# MCU.net
KiCad netlist of a schematic drawn in Altium Designer
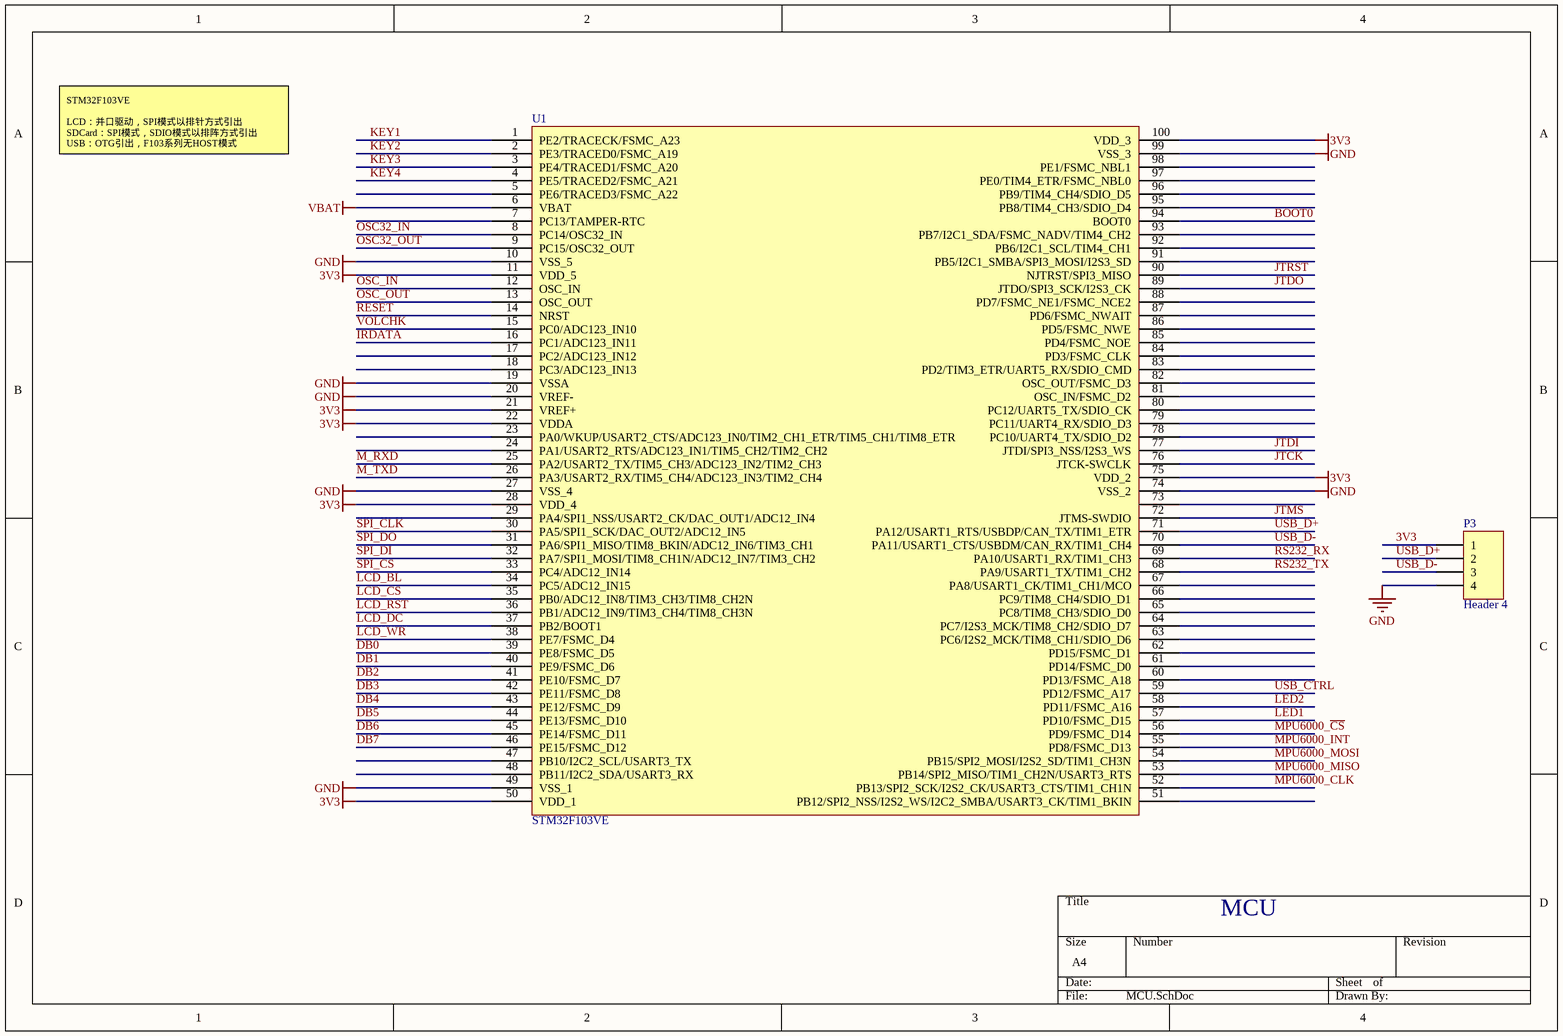
[diagram p0: MCU.SchDoc]

(export (version "E")
  (design (tool "Eeschema 10.0.6"))
  (components
    (comp (ref "P3")
      (value "Header 4")
      (footprint "HDR1X4")
      (description "Header, 4-Pin")
      (fields (field (name "PUBLISHER") "Altium Limited"))
      (libsource (lib "Miscellaneous Connectors") (part "Header 4"))
    )
    (comp (ref "U1")
      (value "STM32F103VE")
      (footprint "LQFP100_M")
      (libsource (lib "STM32F103VE") (part "STM32F103VE"))
    )
  )
  (nets
    (net (code "1") (name "/BOOT0") (class "Default")
      (node (ref "U1") (pin "94") (pinfunction "BOOT0_94") (pintype "passive"))
    )
    (net (code "2") (name "/DB0") (class "Default")
      (node (ref "U1") (pin "39") (pinfunction "PE8/FSMC_D5_39") (pintype "passive"))
    )
    (net (code "3") (name "/DB1") (class "Default")
      (node (ref "U1") (pin "40") (pinfunction "PE9/FSMC_D6_40") (pintype "passive"))
    )
    (net (code "4") (name "/DB2") (class "Default")
      (node (ref "U1") (pin "41") (pinfunction "PE10/FSMC_D7_41") (pintype "passive"))
    )
    (net (code "5") (name "/DB3") (class "Default")
      (node (ref "U1") (pin "42") (pinfunction "PE11/FSMC_D8_42") (pintype "passive"))
    )
    (net (code "6") (name "/DB4") (class "Default")
      (node (ref "U1") (pin "43") (pinfunction "PE12/FSMC_D9_43") (pintype "passive"))
    )
    (net (code "7") (name "/DB5") (class "Default")
      (node (ref "U1") (pin "44") (pinfunction "PE13/FSMC_D10_44") (pintype "passive"))
    )
    (net (code "8") (name "/DB6") (class "Default")
      (node (ref "U1") (pin "45") (pinfunction "PE14/FSMC_D11_45") (pintype "passive"))
    )
    (net (code "9") (name "/DB7") (class "Default")
      (node (ref "U1") (pin "46") (pinfunction "PE15/FSMC_D12_46") (pintype "passive"))
    )
    (net (code "10") (name "/IRDATA") (class "Default")
      (node (ref "U1") (pin "16") (pinfunction "PC1/ADC123_IN11_16") (pintype "passive"))
    )
    (net (code "11") (name "/JTCK") (class "Default")
      (node (ref "U1") (pin "76") (pinfunction "JTCK-SWCLK_76") (pintype "passive"))
    )
    (net (code "12") (name "/JTDI") (class "Default")
      (node (ref "U1") (pin "77") (pinfunction "JTDI/SPI3_NSS/I2S3_WS_77") (pintype "passive"))
    )
    (net (code "13") (name "/JTDO") (class "Default")
      (node (ref "U1") (pin "89") (pinfunction "JTDO/SPI3_SCK/I2S3_CK_89") (pintype "passive"))
    )
    (net (code "14") (name "/JTMS") (class "Default")
      (node (ref "U1") (pin "72") (pinfunction "JTMS-SWDIO_72") (pintype "passive"))
    )
    (net (code "15") (name "/JTRST") (class "Default")
      (node (ref "U1") (pin "90") (pinfunction "NJTRST/SPI3_MISO_90") (pintype "passive"))
    )
    (net (code "16") (name "/KEY1") (class "Default")
      (node (ref "U1") (pin "1") (pinfunction "PE2/TRACECK/FSMC_A23_1") (pintype "passive"))
    )
    (net (code "17") (name "/KEY2") (class "Default")
      (node (ref "U1") (pin "2") (pinfunction "PE3/TRACED0/FSMC_A19_2") (pintype "passive"))
    )
    (net (code "18") (name "/KEY3") (class "Default")
      (node (ref "U1") (pin "3") (pinfunction "PE4/TRACED1/FSMC_A20_3") (pintype "passive"))
    )
    (net (code "19") (name "/KEY4") (class "Default")
      (node (ref "U1") (pin "4") (pinfunction "PE5/TRACED2/FSMC_A21_4") (pintype "passive"))
    )
    (net (code "20") (name "/LCD_BL") (class "Default")
      (node (ref "U1") (pin "34") (pinfunction "PC5/ADC12_IN15_34") (pintype "passive"))
    )
    (net (code "21") (name "/LCD_CS") (class "Default")
      (node (ref "U1") (pin "35") (pinfunction "PB0/ADC12_IN8/TIM3_CH3/TIM8_CH2N_35") (pintype "passive"))
    )
    (net (code "22") (name "/LCD_DC") (class "Default")
      (node (ref "U1") (pin "37") (pinfunction "PB2/BOOT1_37") (pintype "passive"))
    )
    (net (code "23") (name "/LCD_RST") (class "Default")
      (node (ref "U1") (pin "36") (pinfunction "PB1/ADC12_IN9/TIM3_CH4/TIM8_CH3N_36") (pintype "passive"))
    )
    (net (code "24") (name "/LCD_WR") (class "Default")
      (node (ref "U1") (pin "38") (pinfunction "PE7/FSMC_D4_38") (pintype "passive"))
    )
    (net (code "25") (name "/LED1") (class "Default")
      (node (ref "U1") (pin "57") (pinfunction "PD10/FSMC_D15_57") (pintype "passive"))
    )
    (net (code "26") (name "/LED2") (class "Default")
      (node (ref "U1") (pin "58") (pinfunction "PD11/FSMC_A16_58") (pintype "passive"))
    )
    (net (code "27") (name "/MPU6000_CLK") (class "Default")
      (node (ref "U1") (pin "52") (pinfunction "PB13/SPI2_SCK/I2S2_CK/USART3_CTS/TIM1_CH1N_52") (pintype "passive"))
    )
    (net (code "28") (name "/MPU6000_INT") (class "Default")
      (node (ref "U1") (pin "55") (pinfunction "PD8/FSMC_D13_55") (pintype "passive"))
    )
    (net (code "29") (name "/MPU6000_MISO") (class "Default")
      (node (ref "U1") (pin "53") (pinfunction "PB14/SPI2_MISO/TIM1_CH2N/USART3_RTS_53") (pintype "passive"))
    )
    (net (code "30") (name "/MPU6000_MOSI") (class "Default")
      (node (ref "U1") (pin "54") (pinfunction "PB15/SPI2_MOSI/I2S2_SD/TIM1_CH3N_54") (pintype "passive"))
    )
    (net (code "31") (name "/MPU6000_~{CS}") (class "Default")
      (node (ref "U1") (pin "56") (pinfunction "PD9/FSMC_D14_56") (pintype "passive"))
    )
    (net (code "32") (name "/M_RXD") (class "Default")
      (node (ref "U1") (pin "25") (pinfunction "PA2/USART2_TX/TIM5_CH3/ADC123_IN2/TIM2_CH3_25") (pintype "passive"))
    )
    (net (code "33") (name "/M_TXD") (class "Default")
      (node (ref "U1") (pin "26") (pinfunction "PA3/USART2_RX/TIM5_CH4/ADC123_IN3/TIM2_CH4_26") (pintype "passive"))
    )
    (net (code "34") (name "/OSC32_IN") (class "Default")
      (node (ref "U1") (pin "8") (pinfunction "PC14/OSC32_IN_8") (pintype "passive"))
    )
    (net (code "35") (name "/OSC32_OUT") (class "Default")
      (node (ref "U1") (pin "9") (pinfunction "PC15/OSC32_OUT_9") (pintype "passive"))
    )
    (net (code "36") (name "/OSC_IN") (class "Default")
      (node (ref "U1") (pin "12") (pinfunction "OSC_IN_12") (pintype "passive"))
    )
    (net (code "37") (name "/OSC_OUT") (class "Default")
      (node (ref "U1") (pin "13") (pinfunction "OSC_OUT_13") (pintype "passive"))
    )
    (net (code "38") (name "/RESET") (class "Default")
      (node (ref "U1") (pin "14") (pinfunction "NRST_14") (pintype "passive"))
    )
    (net (code "39") (name "/RS232_RX") (class "Default")
      (node (ref "U1") (pin "69") (pinfunction "PA10/USART1_RX/TIM1_CH3_69") (pintype "passive"))
    )
    (net (code "40") (name "/RS232_TX") (class "Default")
      (node (ref "U1") (pin "68") (pinfunction "PA9/USART1_TX/TIM1_CH2_68") (pintype "passive"))
    )
    (net (code "41") (name "/SPI_CLK") (class "Default")
      (node (ref "U1") (pin "30") (pinfunction "PA5/SPI1_SCK/DAC_OUT2/ADC12_IN5_30") (pintype "passive"))
    )
    (net (code "42") (name "/SPI_DI") (class "Default")
      (node (ref "U1") (pin "32") (pinfunction "PA7/SPI1_MOSI/TIM8_CH1N/ADC12_IN7/TIM3_CH2_32") (pintype "passive"))
    )
    (net (code "43") (name "/SPI_DO") (class "Default")
      (node (ref "U1") (pin "31") (pinfunction "PA6/SPI1_MISO/TIM8_BKIN/ADC12_IN6/TIM3_CH1_31") (pintype "passive"))
    )
    (net (code "44") (name "/SPI_~{CS}") (class "Default")
      (node (ref "U1") (pin "33") (pinfunction "PC4/ADC12_IN14_33") (pintype "passive"))
    )
    (net (code "45") (name "/USB_CTRL") (class "Default")
      (node (ref "U1") (pin "59") (pinfunction "PD12/FSMC_A17_59") (pintype "passive"))
    )
    (net (code "46") (name "/USB_D+") (class "Default")
      (node (ref "P3") (pin "2") (pinfunction "2_2") (pintype "passive"))
      (node (ref "U1") (pin "71") (pinfunction "PA12/USART1_RTS/USBDP/CAN_TX/TIM1_ETR_71") (pintype "passive"))
    )
    (net (code "47") (name "/USB_D-") (class "Default")
      (node (ref "P3") (pin "3") (pinfunction "3_3") (pintype "passive"))
      (node (ref "U1") (pin "70") (pinfunction "PA11/USART1_CTS/USBDM/CAN_RX/TIM1_CH4_70") (pintype "passive"))
    )
    (net (code "48") (name "/VOLCHK") (class "Default")
      (node (ref "U1") (pin "15") (pinfunction "PC0/ADC123_IN10_15") (pintype "passive"))
    )
    (net (code "49") (name "3V3") (class "Default")
      (node (ref "P3") (pin "1") (pinfunction "1_1") (pintype "passive"))
      (node (ref "U1") (pin "100") (pinfunction "VDD_3_100") (pintype "passive"))
      (node (ref "U1") (pin "11") (pinfunction "VDD_5_11") (pintype "passive"))
      (node (ref "U1") (pin "21") (pinfunction "VREF+_21") (pintype "passive"))
      (node (ref "U1") (pin "22") (pinfunction "VDDA_22") (pintype "passive"))
      (node (ref "U1") (pin "28") (pinfunction "VDD_4_28") (pintype "passive"))
      (node (ref "U1") (pin "50") (pinfunction "VDD_1_50") (pintype "passive"))
      (node (ref "U1") (pin "75") (pinfunction "VDD_2_75") (pintype "passive"))
    )
    (net (code "50") (name "GND") (class "Default")
      (node (ref "P3") (pin "4") (pinfunction "4_4") (pintype "passive"))
      (node (ref "U1") (pin "10") (pinfunction "VSS_5_10") (pintype "passive"))
      (node (ref "U1") (pin "19") (pinfunction "VSSA_19") (pintype "passive"))
      (node (ref "U1") (pin "20") (pinfunction "VREF-_20") (pintype "passive"))
      (node (ref "U1") (pin "27") (pinfunction "VSS_4_27") (pintype "passive"))
      (node (ref "U1") (pin "49") (pinfunction "VSS_1_49") (pintype "passive"))
      (node (ref "U1") (pin "74") (pinfunction "VSS_2_74") (pintype "passive"))
      (node (ref "U1") (pin "99") (pinfunction "VSS_3_99") (pintype "passive"))
    )
    (net (code "51") (name "VBAT") (class "Default")
      (node (ref "U1") (pin "6") (pinfunction "VBAT_6") (pintype "passive"))
    )
    (net (code "52") (name "unconnected-(U1-OSC_IN{slash}FSMC_D2-Pad81)") (class "Default")
      (node (ref "U1") (pin "81") (pinfunction "OSC_IN/FSMC_D2_81") (pintype "passive"))
    )
    (net (code "53") (name "unconnected-(U1-OSC_OUT{slash}FSMC_D3-Pad82)") (class "Default")
      (node (ref "U1") (pin "82") (pinfunction "OSC_OUT/FSMC_D3_82") (pintype "passive"))
    )
    (net (code "54") (name "unconnected-(U1-PA0{slash}WKUP{slash}USART2_CTS{slash}ADC123_IN0{slash}TIM2_CH1_ETR{slash}TIM5_CH1{slash}TIM8_ETR-Pad23)") (class "Default")
      (node (ref "U1") (pin "23") (pinfunction "PA0/WKUP/USART2_CTS/ADC123_IN0/TIM2_CH1_ETR/TIM5_CH1/TIM8_ETR_23") (pintype "passive"))
    )
    (net (code "55") (name "unconnected-(U1-PA1{slash}USART2_RTS{slash}ADC123_IN1{slash}TIM5_CH2{slash}TIM2_CH2-Pad24)") (class "Default")
      (node (ref "U1") (pin "24") (pinfunction "PA1/USART2_RTS/ADC123_IN1/TIM5_CH2/TIM2_CH2_24") (pintype "passive"))
    )
    (net (code "56") (name "unconnected-(U1-PA4{slash}SPI1_NSS{slash}USART2_CK{slash}DAC_OUT1{slash}ADC12_IN4-Pad29)") (class "Default")
      (node (ref "U1") (pin "29") (pinfunction "PA4/SPI1_NSS/USART2_CK/DAC_OUT1/ADC12_IN4_29") (pintype "passive"))
    )
    (net (code "57") (name "unconnected-(U1-PA8{slash}USART1_CK{slash}TIM1_CH1{slash}MCO-Pad67)") (class "Default")
      (node (ref "U1") (pin "67") (pinfunction "PA8/USART1_CK/TIM1_CH1/MCO_67") (pintype "passive"))
    )
    (net (code "58") (name "unconnected-(U1-PB5{slash}I2C1_SMBA{slash}SPI3_MOSI{slash}I2S3_SD-Pad91)") (class "Default")
      (node (ref "U1") (pin "91") (pinfunction "PB5/I2C1_SMBA/SPI3_MOSI/I2S3_SD_91") (pintype "passive"))
    )
    (net (code "59") (name "unconnected-(U1-PB6{slash}I2C1_SCL{slash}TIM4_CH1-Pad92)") (class "Default")
      (node (ref "U1") (pin "92") (pinfunction "PB6/I2C1_SCL/TIM4_CH1_92") (pintype "passive"))
    )
    (net (code "60") (name "unconnected-(U1-PB7{slash}I2C1_SDA{slash}FSMC_NADV{slash}TIM4_CH2-Pad93)") (class "Default")
      (node (ref "U1") (pin "93") (pinfunction "PB7/I2C1_SDA/FSMC_NADV/TIM4_CH2_93") (pintype "passive"))
    )
    (net (code "61") (name "unconnected-(U1-PB8{slash}TIM4_CH3{slash}SDIO_D4-Pad95)") (class "Default")
      (node (ref "U1") (pin "95") (pinfunction "PB8/TIM4_CH3/SDIO_D4_95") (pintype "passive"))
    )
    (net (code "62") (name "unconnected-(U1-PB9{slash}TIM4_CH4{slash}SDIO_D5-Pad96)") (class "Default")
      (node (ref "U1") (pin "96") (pinfunction "PB9/TIM4_CH4/SDIO_D5_96") (pintype "passive"))
    )
    (net (code "63") (name "unconnected-(U1-PB10{slash}I2C2_SCL{slash}USART3_TX-Pad47)") (class "Default")
      (node (ref "U1") (pin "47") (pinfunction "PB10/I2C2_SCL/USART3_TX_47") (pintype "passive"))
    )
    (net (code "64") (name "unconnected-(U1-PB11{slash}I2C2_SDA{slash}USART3_RX-Pad48)") (class "Default")
      (node (ref "U1") (pin "48") (pinfunction "PB11/I2C2_SDA/USART3_RX_48") (pintype "passive"))
    )
    (net (code "65") (name "unconnected-(U1-PB12{slash}SPI2_NSS{slash}I2S2_WS{slash}I2C2_SMBA{slash}USART3_CK{slash}TIM1_BKIN-Pad51)") (class "Default")
      (node (ref "U1") (pin "51") (pinfunction "PB12/SPI2_NSS/I2S2_WS/I2C2_SMBA/USART3_CK/TIM1_BKIN_51") (pintype "passive"))
    )
    (net (code "66") (name "unconnected-(U1-PC2{slash}ADC123_IN12-Pad17)") (class "Default")
      (node (ref "U1") (pin "17") (pinfunction "PC2/ADC123_IN12_17") (pintype "passive"))
    )
    (net (code "67") (name "unconnected-(U1-PC3{slash}ADC123_IN13-Pad18)") (class "Default")
      (node (ref "U1") (pin "18") (pinfunction "PC3/ADC123_IN13_18") (pintype "passive"))
    )
    (net (code "68") (name "unconnected-(U1-PC6{slash}I2S2_MCK{slash}TIM8_CH1{slash}SDIO_D6-Pad63)") (class "Default")
      (node (ref "U1") (pin "63") (pinfunction "PC6/I2S2_MCK/TIM8_CH1/SDIO_D6_63") (pintype "passive"))
    )
    (net (code "69") (name "unconnected-(U1-PC7{slash}I2S3_MCK{slash}TIM8_CH2{slash}SDIO_D7-Pad64)") (class "Default")
      (node (ref "U1") (pin "64") (pinfunction "PC7/I2S3_MCK/TIM8_CH2/SDIO_D7_64") (pintype "passive"))
    )
    (net (code "70") (name "unconnected-(U1-PC8{slash}TIM8_CH3{slash}SDIO_D0-Pad65)") (class "Default")
      (node (ref "U1") (pin "65") (pinfunction "PC8/TIM8_CH3/SDIO_D0_65") (pintype "passive"))
    )
    (net (code "71") (name "unconnected-(U1-PC9{slash}TIM8_CH4{slash}SDIO_D1-Pad66)") (class "Default")
      (node (ref "U1") (pin "66") (pinfunction "PC9/TIM8_CH4/SDIO_D1_66") (pintype "passive"))
    )
    (net (code "72") (name "unconnected-(U1-PC10{slash}UART4_TX{slash}SDIO_D2-Pad78)") (class "Default")
      (node (ref "U1") (pin "78") (pinfunction "PC10/UART4_TX/SDIO_D2_78") (pintype "passive"))
    )
    (net (code "73") (name "unconnected-(U1-PC11{slash}UART4_RX{slash}SDIO_D3-Pad79)") (class "Default")
      (node (ref "U1") (pin "79") (pinfunction "PC11/UART4_RX/SDIO_D3_79") (pintype "passive"))
    )
    (net (code "74") (name "unconnected-(U1-PC12{slash}UART5_TX{slash}SDIO_CK-Pad80)") (class "Default")
      (node (ref "U1") (pin "80") (pinfunction "PC12/UART5_TX/SDIO_CK_80") (pintype "passive"))
    )
    (net (code "75") (name "unconnected-(U1-PC13{slash}TAMPER-RTC-Pad7)") (class "Default")
      (node (ref "U1") (pin "7") (pinfunction "PC13/TAMPER-RTC_7") (pintype "passive"))
    )
    (net (code "76") (name "unconnected-(U1-PD2{slash}TIM3_ETR{slash}UART5_RX{slash}SDIO_CMD-Pad83)") (class "Default")
      (node (ref "U1") (pin "83") (pinfunction "PD2/TIM3_ETR/UART5_RX/SDIO_CMD_83") (pintype "passive"))
    )
    (net (code "77") (name "unconnected-(U1-PD3{slash}FSMC_CLK-Pad84)") (class "Default")
      (node (ref "U1") (pin "84") (pinfunction "PD3/FSMC_CLK_84") (pintype "passive"))
    )
    (net (code "78") (name "unconnected-(U1-PD4{slash}FSMC_NOE-Pad85)") (class "Default")
      (node (ref "U1") (pin "85") (pinfunction "PD4/FSMC_NOE_85") (pintype "passive"))
    )
    (net (code "79") (name "unconnected-(U1-PD5{slash}FSMC_NWE-Pad86)") (class "Default")
      (node (ref "U1") (pin "86") (pinfunction "PD5/FSMC_NWE_86") (pintype "passive"))
    )
    (net (code "80") (name "unconnected-(U1-PD6{slash}FSMC_NWAIT-Pad87)") (class "Default")
      (node (ref "U1") (pin "87") (pinfunction "PD6/FSMC_NWAIT_87") (pintype "passive"))
    )
    (net (code "81") (name "unconnected-(U1-PD7{slash}FSMC_NE1{slash}FSMC_NCE2-Pad88)") (class "Default")
      (node (ref "U1") (pin "88") (pinfunction "PD7/FSMC_NE1/FSMC_NCE2_88") (pintype "passive"))
    )
    (net (code "82") (name "unconnected-(U1-PD13{slash}FSMC_A18-Pad60)") (class "Default")
      (node (ref "U1") (pin "60") (pinfunction "PD13/FSMC_A18_60") (pintype "passive"))
    )
    (net (code "83") (name "unconnected-(U1-PD14{slash}FSMC_D0-Pad61)") (class "Default")
      (node (ref "U1") (pin "61") (pinfunction "PD14/FSMC_D0_61") (pintype "passive"))
    )
    (net (code "84") (name "unconnected-(U1-PD15{slash}FSMC_D1-Pad62)") (class "Default")
      (node (ref "U1") (pin "62") (pinfunction "PD15/FSMC_D1_62") (pintype "passive"))
    )
    (net (code "85") (name "unconnected-(U1-PE0{slash}TIM4_ETR{slash}FSMC_NBL0-Pad97)") (class "Default")
      (node (ref "U1") (pin "97") (pinfunction "PE0/TIM4_ETR/FSMC_NBL0_97") (pintype "passive"))
    )
    (net (code "86") (name "unconnected-(U1-PE1{slash}FSMC_NBL1-Pad98)") (class "Default")
      (node (ref "U1") (pin "98") (pinfunction "PE1/FSMC_NBL1_98") (pintype "passive"))
    )
    (net (code "87") (name "unconnected-(U1-PE6{slash}TRACED3{slash}FSMC_A22-Pad5)") (class "Default")
      (node (ref "U1") (pin "5") (pinfunction "PE6/TRACED3/FSMC_A22_5") (pintype "passive"))
    )
    (net (code "88") (name "unconnected-(U1-Pad73)") (class "Default")
      (node (ref "U1") (pin "73") (pintype "passive"))
    )
  )
)
